# pumpShield.net
KiCad netlist of a schematic drawn in EAGLE
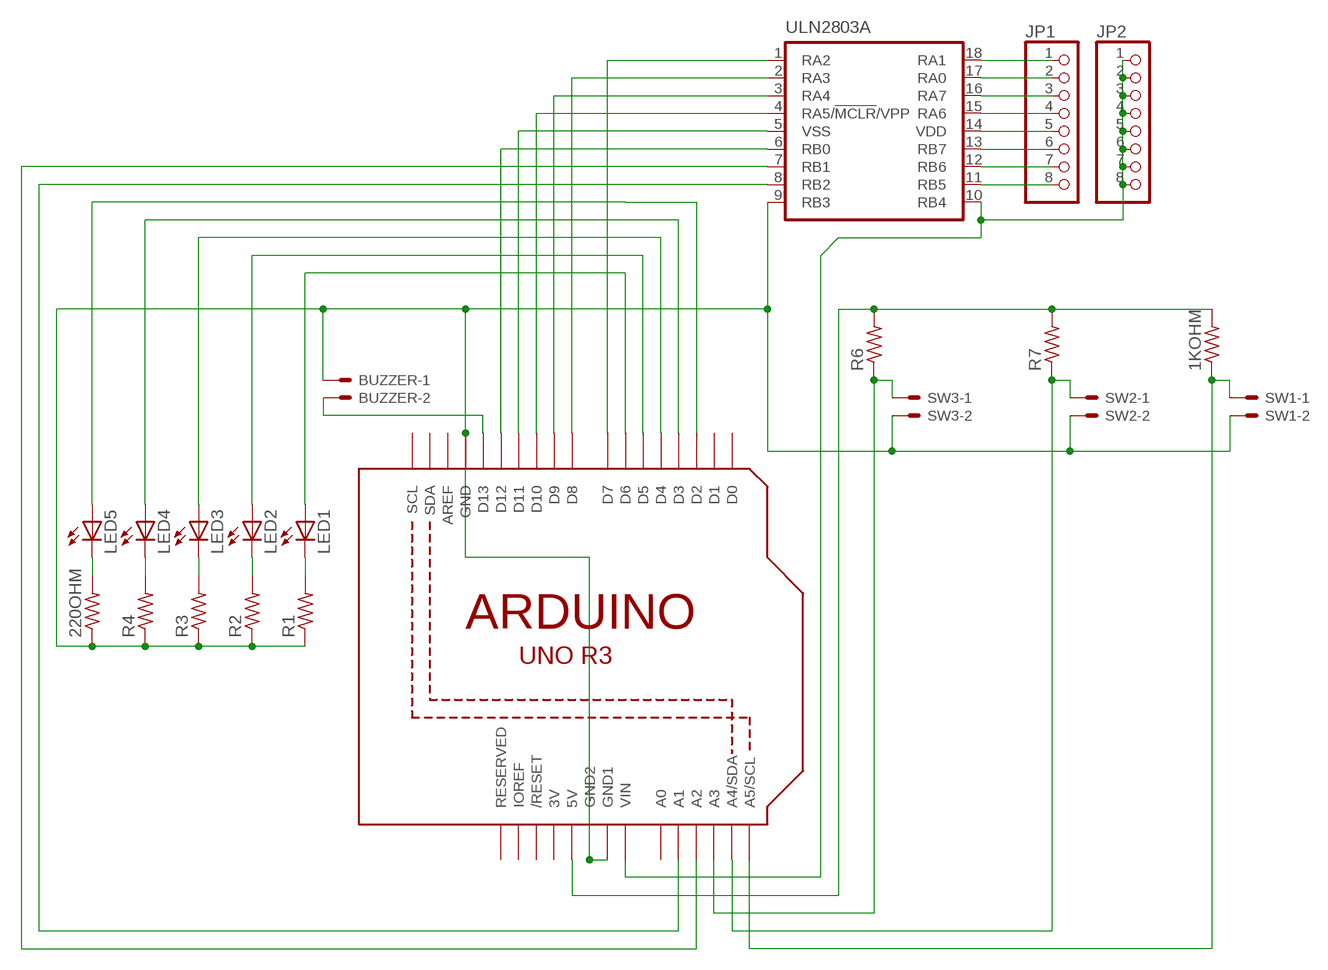
[diagram p0: schematic, sheet 1]

(export (version "E")
  (design (tool "Eeschema 10.0.6"))
  (components
    (comp (ref "1KOHM")
      (value "R-US_0207/9")
      (footprint "eagle-import:0207_9")
      (libsource (lib "eagle-import") (part "R-US_0207/9"))
    )
    (comp (ref "220OHM")
      (value "R-US_0207/9")
      (footprint "eagle-import:0207_9")
      (libsource (lib "eagle-import") (part "R-US_0207/9"))
    )
    (comp (ref "BUZZER")
      (value "22-23-2021")
      (footprint "eagle-import:22-23-2021")
      (fields (field (name "MF") "MOLEX"))
      (libsource (lib "eagle-import") (part "22-23-2021"))
    )
    (comp (ref "JP1")
      (value "PINHD-1X8CLEANBIG")
      (footprint "eagle-import:1X08-CLEANBIG")
      (libsource (lib "eagle-import") (part "PINHD-1X8CLEANBIG"))
    )
    (comp (ref "JP2")
      (value "PINHD-1X8CLEANBIG")
      (footprint "eagle-import:1X08-CLEANBIG")
      (libsource (lib "eagle-import") (part "PINHD-1X8CLEANBIG"))
    )
    (comp (ref "LED1")
      (value "LED3MM")
      (footprint "eagle-import:LED3MM")
      (libsource (lib "eagle-import") (part "LED3MM"))
    )
    (comp (ref "LED2")
      (value "LED3MM")
      (footprint "eagle-import:LED3MM")
      (libsource (lib "eagle-import") (part "LED3MM"))
    )
    (comp (ref "LED3")
      (value "LED3MM")
      (footprint "eagle-import:LED3MM")
      (libsource (lib "eagle-import") (part "LED3MM"))
    )
    (comp (ref "LED4")
      (value "LED3MM")
      (footprint "eagle-import:LED3MM")
      (libsource (lib "eagle-import") (part "LED3MM"))
    )
    (comp (ref "LED5")
      (value "LED3MM")
      (footprint "eagle-import:LED3MM")
      (libsource (lib "eagle-import") (part "LED3MM"))
    )
    (comp (ref "R1")
      (value "R-US_0207/9")
      (footprint "eagle-import:0207_9")
      (libsource (lib "eagle-import") (part "R-US_0207/9"))
    )
    (comp (ref "R2")
      (value "R-US_0207/9")
      (footprint "eagle-import:0207_9")
      (libsource (lib "eagle-import") (part "R-US_0207/9"))
    )
    (comp (ref "R3")
      (value "R-US_0207/9")
      (footprint "eagle-import:0207_9")
      (libsource (lib "eagle-import") (part "R-US_0207/9"))
    )
    (comp (ref "R4")
      (value "R-US_0207/9")
      (footprint "eagle-import:0207_9")
      (libsource (lib "eagle-import") (part "R-US_0207/9"))
    )
    (comp (ref "R6")
      (value "R-US_0207/9")
      (footprint "eagle-import:0207_9")
      (libsource (lib "eagle-import") (part "R-US_0207/9"))
    )
    (comp (ref "R7")
      (value "R-US_0207/9")
      (footprint "eagle-import:0207_9")
      (libsource (lib "eagle-import") (part "R-US_0207/9"))
    )
    (comp (ref "SW1")
      (value "22-23-2021")
      (footprint "eagle-import:22-23-2021")
      (fields (field (name "MF") "MOLEX"))
      (libsource (lib "eagle-import") (part "22-23-2021"))
    )
    (comp (ref "SW2")
      (value "22-23-2021")
      (footprint "eagle-import:22-23-2021")
      (fields (field (name "MF") "MOLEX"))
      (libsource (lib "eagle-import") (part "22-23-2021"))
    )
    (comp (ref "SW3")
      (value "22-23-2021")
      (footprint "eagle-import:22-23-2021")
      (fields (field (name "MF") "MOLEX"))
      (libsource (lib "eagle-import") (part "22-23-2021"))
    )
    (comp (ref "U1")
      (value "ARDUINOR3-DIMENSION")
      (footprint "eagle-import:ARDUINOR3")
      (libsource (lib "eagle-import") (part "ARDUINOR3-DIMENSION"))
    )
    (comp (ref "ULN2803A")
      (value "PIC16F1826/27P")
      (footprint "eagle-import:DIL18")
      (libsource (lib "eagle-import") (part "PIC16F1826/27P"))
    )
  )
  (nets
    (net (code "1") (name "/3V") (class "Default")
      (node (ref "U1") (pin "3V") (pinfunction "3V_3V") (pintype "power_in"))
    )
    (net (code "2") (name "Net-(1KOHM-Pad2)") (class "Default")
      (node (ref "1KOHM") (pin "2") (pinfunction "2_2") (pintype "passive"))
      (node (ref "R6") (pin "2") (pinfunction "2_2") (pintype "passive"))
      (node (ref "R7") (pin "2") (pinfunction "2_2") (pintype "passive"))
      (node (ref "U1") (pin "5V") (pinfunction "5V_5V") (pintype "power_in"))
    )
    (net (code "3") (name "Net-(BUZZERA-S)") (class "Default")
      (node (ref "220OHM") (pin "1") (pinfunction "1_1") (pintype "passive"))
      (node (ref "BUZZER") (pin "1") (pinfunction "S_1") (pintype "passive"))
      (node (ref "R1") (pin "1") (pinfunction "1_1") (pintype "passive"))
      (node (ref "R2") (pin "1") (pinfunction "1_1") (pintype "passive"))
      (node (ref "R3") (pin "1") (pinfunction "1_1") (pintype "passive"))
      (node (ref "R4") (pin "1") (pinfunction "1_1") (pintype "passive"))
      (node (ref "SW1") (pin "2") (pinfunction "S_2") (pintype "passive"))
      (node (ref "SW2") (pin "2") (pinfunction "S_2") (pintype "passive"))
      (node (ref "SW3") (pin "2") (pinfunction "S_2") (pintype "passive"))
      (node (ref "U1") (pin "GND") (pinfunction "GND_GND") (pintype "power_in"))
      (node (ref "U1") (pin "GND1") (pinfunction "GND1_GND1") (pintype "power_in"))
      (node (ref "U1") (pin "GND2") (pinfunction "GND2_GND2") (pintype "power_in"))
      (node (ref "ULN2803A") (pin "9") (pinfunction "RB3_9") (pintype "bidirectional"))
    )
    (net (code "4") (name "Net-(BUZZERB-S)") (class "Default")
      (node (ref "BUZZER") (pin "2") (pinfunction "S_2") (pintype "passive"))
      (node (ref "U1") (pin "D13") (pinfunction "D13_D13") (pintype "bidirectional"))
    )
    (net (code "5") (name "Net-(LED1-C)") (class "Default")
      (node (ref "LED1") (pin "K") (pinfunction "C_K") (pintype "passive"))
      (node (ref "R1") (pin "2") (pinfunction "2_2") (pintype "passive"))
    )
    (net (code "6") (name "Net-(LED1-PadA)") (class "Default")
      (node (ref "LED1") (pin "A") (pinfunction "A_A") (pintype "passive"))
      (node (ref "U1") (pin "D6") (pinfunction "D6_D6") (pintype "bidirectional"))
    )
    (net (code "7") (name "Net-(LED2-C)") (class "Default")
      (node (ref "LED2") (pin "K") (pinfunction "C_K") (pintype "passive"))
      (node (ref "R2") (pin "2") (pinfunction "2_2") (pintype "passive"))
    )
    (net (code "8") (name "Net-(LED2-PadA)") (class "Default")
      (node (ref "LED2") (pin "A") (pinfunction "A_A") (pintype "passive"))
      (node (ref "U1") (pin "D5") (pinfunction "D5_D5") (pintype "bidirectional"))
    )
    (net (code "9") (name "Net-(LED3-C)") (class "Default")
      (node (ref "LED3") (pin "K") (pinfunction "C_K") (pintype "passive"))
      (node (ref "R3") (pin "2") (pinfunction "2_2") (pintype "passive"))
    )
    (net (code "10") (name "Net-(LED3-PadA)") (class "Default")
      (node (ref "LED3") (pin "A") (pinfunction "A_A") (pintype "passive"))
      (node (ref "U1") (pin "D4") (pinfunction "D4_D4") (pintype "bidirectional"))
    )
    (net (code "11") (name "Net-(LED4-C)") (class "Default")
      (node (ref "LED4") (pin "K") (pinfunction "C_K") (pintype "passive"))
      (node (ref "R4") (pin "2") (pinfunction "2_2") (pintype "passive"))
    )
    (net (code "12") (name "Net-(LED4-PadA)") (class "Default")
      (node (ref "LED4") (pin "A") (pinfunction "A_A") (pintype "passive"))
      (node (ref "U1") (pin "D3") (pinfunction "D3_D3") (pintype "bidirectional"))
    )
    (net (code "13") (name "Net-(LED5-C)") (class "Default")
      (node (ref "220OHM") (pin "2") (pinfunction "2_2") (pintype "passive"))
      (node (ref "LED5") (pin "K") (pinfunction "C_K") (pintype "passive"))
    )
    (net (code "14") (name "Net-(LED5-PadA)") (class "Default")
      (node (ref "LED5") (pin "A") (pinfunction "A_A") (pintype "passive"))
      (node (ref "U1") (pin "D2") (pinfunction "D2_D2") (pintype "bidirectional"))
    )
    (net (code "15") (name "Net-(SW1A-S)") (class "Default")
      (node (ref "1KOHM") (pin "1") (pinfunction "1_1") (pintype "passive"))
      (node (ref "SW1") (pin "1") (pinfunction "S_1") (pintype "passive"))
      (node (ref "U1") (pin "A5") (pinfunction "A5/SCL_A5") (pintype "bidirectional"))
    )
    (net (code "16") (name "Net-(SW2A-S)") (class "Default")
      (node (ref "R7") (pin "1") (pinfunction "1_1") (pintype "passive"))
      (node (ref "SW2") (pin "1") (pinfunction "S_1") (pintype "passive"))
      (node (ref "U1") (pin "A4") (pinfunction "A4/SDA_A4") (pintype "bidirectional"))
    )
    (net (code "17") (name "Net-(SW3A-S)") (class "Default")
      (node (ref "R6") (pin "1") (pinfunction "1_1") (pintype "passive"))
      (node (ref "SW3") (pin "1") (pinfunction "S_1") (pintype "passive"))
      (node (ref "U1") (pin "A3") (pinfunction "A3_A3") (pintype "bidirectional"))
    )
    (net (code "18") (name "Net-(ULN2803A-RA0)") (class "Default")
      (node (ref "JP1") (pin "2") (pinfunction "2_2") (pintype "passive"))
      (node (ref "ULN2803A") (pin "17") (pinfunction "RA0_17") (pintype "bidirectional"))
    )
    (net (code "19") (name "Net-(ULN2803A-RA1)") (class "Default")
      (node (ref "JP1") (pin "1") (pinfunction "1_1") (pintype "passive"))
      (node (ref "ULN2803A") (pin "18") (pinfunction "RA1_18") (pintype "bidirectional"))
    )
    (net (code "20") (name "Net-(ULN2803A-RA2)") (class "Default")
      (node (ref "U1") (pin "D7") (pinfunction "D7_D7") (pintype "bidirectional"))
      (node (ref "ULN2803A") (pin "1") (pinfunction "RA2_1") (pintype "bidirectional"))
    )
    (net (code "21") (name "Net-(ULN2803A-RA3)") (class "Default")
      (node (ref "U1") (pin "D8") (pinfunction "D8_D8") (pintype "bidirectional"))
      (node (ref "ULN2803A") (pin "2") (pinfunction "RA3_2") (pintype "bidirectional"))
    )
    (net (code "22") (name "Net-(ULN2803A-RA4)") (class "Default")
      (node (ref "U1") (pin "D9") (pinfunction "D9_D9") (pintype "bidirectional"))
      (node (ref "ULN2803A") (pin "3") (pinfunction "RA4_3") (pintype "bidirectional"))
    )
    (net (code "23") (name "Net-(ULN2803A-RA5{slash}~{MCLR}{slash}VPP)") (class "Default")
      (node (ref "U1") (pin "D10") (pinfunction "D10_D10") (pintype "bidirectional"))
      (node (ref "ULN2803A") (pin "4") (pinfunction "RA5/~{MCLR}/VPP_4") (pintype "bidirectional"))
    )
    (net (code "24") (name "Net-(ULN2803A-RA6)") (class "Default")
      (node (ref "JP1") (pin "4") (pinfunction "4_4") (pintype "passive"))
      (node (ref "ULN2803A") (pin "15") (pinfunction "RA6_15") (pintype "bidirectional"))
    )
    (net (code "25") (name "Net-(ULN2803A-RA7)") (class "Default")
      (node (ref "JP1") (pin "3") (pinfunction "3_3") (pintype "passive"))
      (node (ref "ULN2803A") (pin "16") (pinfunction "RA7_16") (pintype "bidirectional"))
    )
    (net (code "26") (name "Net-(ULN2803A-RB0)") (class "Default")
      (node (ref "U1") (pin "D12") (pinfunction "D12_D12") (pintype "bidirectional"))
      (node (ref "ULN2803A") (pin "6") (pinfunction "RB0_6") (pintype "bidirectional"))
    )
    (net (code "27") (name "Net-(ULN2803A-RB1)") (class "Default")
      (node (ref "U1") (pin "A2") (pinfunction "A2_A2") (pintype "bidirectional"))
      (node (ref "ULN2803A") (pin "7") (pinfunction "RB1_7") (pintype "bidirectional"))
    )
    (net (code "28") (name "Net-(ULN2803A-RB2)") (class "Default")
      (node (ref "U1") (pin "A1") (pinfunction "A1_A1") (pintype "bidirectional"))
      (node (ref "ULN2803A") (pin "8") (pinfunction "RB2_8") (pintype "bidirectional"))
    )
    (net (code "29") (name "Net-(ULN2803A-RB4)") (class "Default")
      (node (ref "JP2") (pin "1") (pinfunction "1_1") (pintype "passive"))
      (node (ref "JP2") (pin "2") (pinfunction "2_2") (pintype "passive"))
      (node (ref "JP2") (pin "3") (pinfunction "3_3") (pintype "passive"))
      (node (ref "JP2") (pin "4") (pinfunction "4_4") (pintype "passive"))
      (node (ref "JP2") (pin "5") (pinfunction "5_5") (pintype "passive"))
      (node (ref "JP2") (pin "6") (pinfunction "6_6") (pintype "passive"))
      (node (ref "JP2") (pin "7") (pinfunction "7_7") (pintype "passive"))
      (node (ref "JP2") (pin "8") (pinfunction "8_8") (pintype "passive"))
      (node (ref "U1") (pin "VIN") (pinfunction "VIN_VIN") (pintype "power_in"))
      (node (ref "ULN2803A") (pin "10") (pinfunction "RB4_10") (pintype "bidirectional"))
    )
    (net (code "30") (name "Net-(ULN2803A-RB5)") (class "Default")
      (node (ref "JP1") (pin "8") (pinfunction "8_8") (pintype "passive"))
      (node (ref "ULN2803A") (pin "11") (pinfunction "RB5_11") (pintype "bidirectional"))
    )
    (net (code "31") (name "Net-(ULN2803A-RB6)") (class "Default")
      (node (ref "JP1") (pin "7") (pinfunction "7_7") (pintype "passive"))
      (node (ref "ULN2803A") (pin "12") (pinfunction "RB6_12") (pintype "bidirectional"))
    )
    (net (code "32") (name "Net-(ULN2803A-RB7)") (class "Default")
      (node (ref "JP1") (pin "6") (pinfunction "6_6") (pintype "passive"))
      (node (ref "ULN2803A") (pin "13") (pinfunction "RB7_13") (pintype "bidirectional"))
    )
    (net (code "33") (name "Net-(ULN2803A-VDD)") (class "Default")
      (node (ref "JP1") (pin "5") (pinfunction "5_5") (pintype "passive"))
      (node (ref "ULN2803A") (pin "14") (pinfunction "VDD_14") (pintype "power_in"))
    )
    (net (code "34") (name "Net-(ULN2803A-VSS)") (class "Default")
      (node (ref "U1") (pin "D11") (pinfunction "D11_D11") (pintype "bidirectional"))
      (node (ref "ULN2803A") (pin "5") (pinfunction "VSS_5") (pintype "power_in"))
    )
    (net (code "35") (name "unconnected-(U1-PadA0)") (class "Default")
      (node (ref "U1") (pin "A0") (pinfunction "A0_A0") (pintype "bidirectional"))
    )
    (net (code "36") (name "unconnected-(U1-PadAREF)") (class "Default")
      (node (ref "U1") (pin "AREF") (pinfunction "AREF_AREF") (pintype "bidirectional"))
    )
    (net (code "37") (name "unconnected-(U1-PadD0)") (class "Default")
      (node (ref "U1") (pin "D0") (pinfunction "D0_D0") (pintype "bidirectional"))
    )
    (net (code "38") (name "unconnected-(U1-PadD1)") (class "Default")
      (node (ref "U1") (pin "D1") (pinfunction "D1_D1") (pintype "bidirectional"))
    )
    (net (code "39") (name "unconnected-(U1-PadIOREF)") (class "Default")
      (node (ref "U1") (pin "IOREF") (pinfunction "IOREF_IOREF") (pintype "output"))
    )
    (net (code "40") (name "unconnected-(U1-PadRESERVED)") (class "Default")
      (node (ref "U1") (pin "RESERVED") (pinfunction "RESERVED_RESERVED") (pintype "no_connect"))
    )
    (net (code "41") (name "unconnected-(U1-PadSCL)") (class "Default")
      (node (ref "U1") (pin "SCL") (pinfunction "SCL_SCL") (pintype "bidirectional"))
    )
    (net (code "42") (name "unconnected-(U1-PadSDA)") (class "Default")
      (node (ref "U1") (pin "SDA") (pinfunction "SDA_SDA") (pintype "bidirectional"))
    )
    (net (code "43") (name "unconnected-(U1-{slash}RESET-PadRESET)") (class "Default")
      (node (ref "U1") (pin "RESET") (pinfunction "/RESET_RESET") (pintype "bidirectional"))
    )
  )
)
